# onekeyboard_2.net
KiCad netlist of a schematic drawn in EAGLE
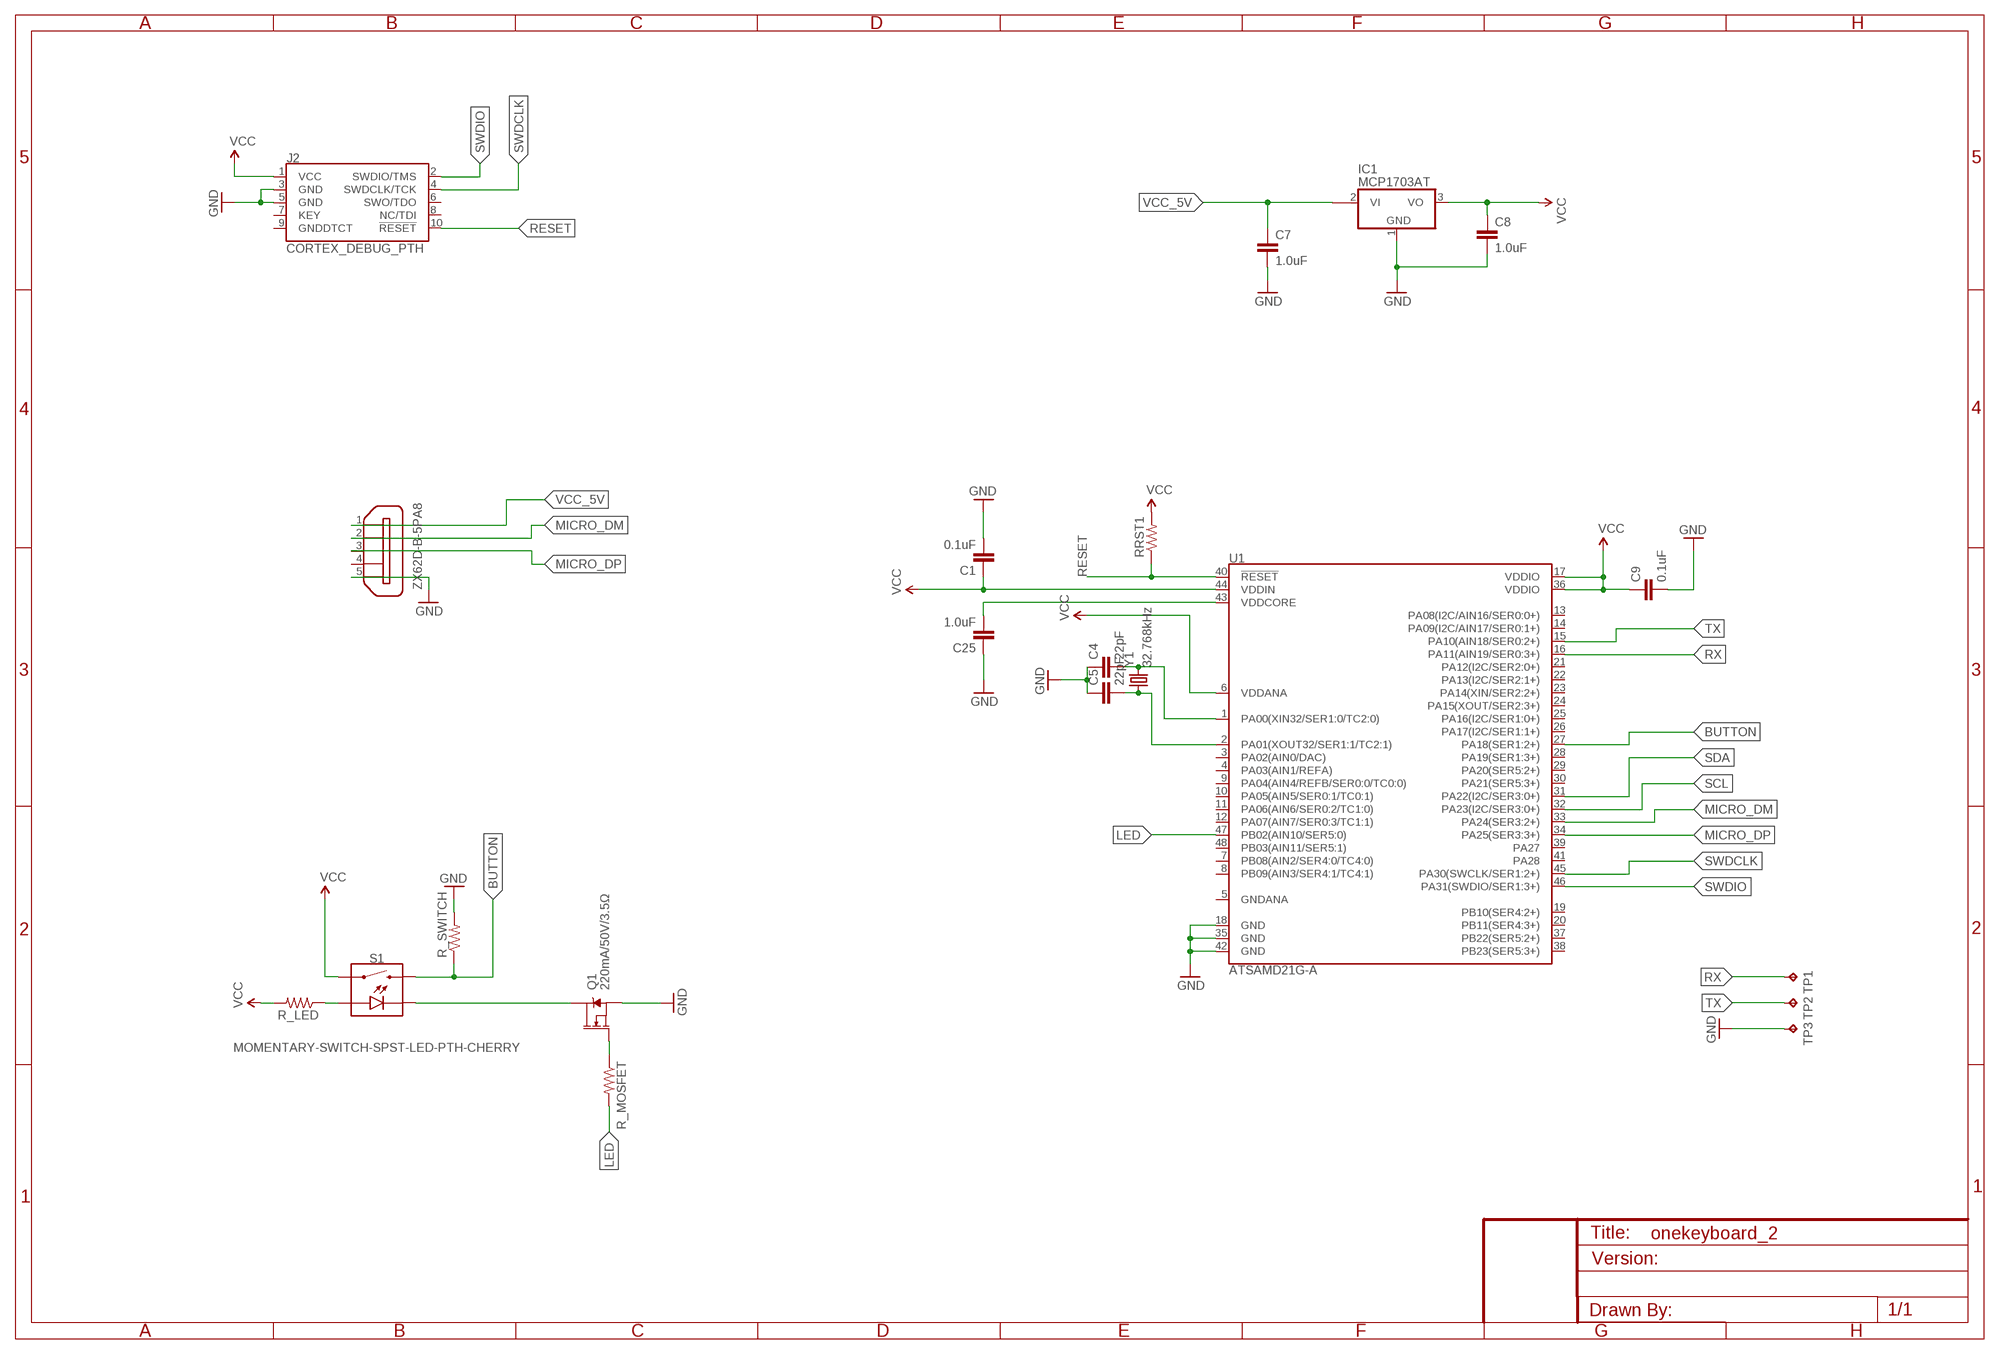
[diagram p0: schematic, sheet 1]

(export (version "E")
  (design (tool "Eeschema 10.0.6"))
  (components
    (comp (ref "C1")
      (value "0.1uF")
      (footprint "eagle-import:0805")
      (libsource (lib "eagle-import") (part "1.0UF-0805-25V-10%"))
    )
    (comp (ref "C4")
      (value "22pF")
      (footprint "eagle-import:0805")
      (libsource (lib "eagle-import") (part "CAP0805"))
    )
    (comp (ref "C5")
      (value "22pF")
      (footprint "eagle-import:0805")
      (libsource (lib "eagle-import") (part "CAP0805"))
    )
    (comp (ref "C7")
      (value "1.0uF")
      (footprint "eagle-import:1206")
      (libsource (lib "eagle-import") (part "1.0UF-1206-50V-10%"))
    )
    (comp (ref "C8")
      (value "1.0uF")
      (footprint "eagle-import:1206")
      (libsource (lib "eagle-import") (part "1.0UF-1206-50V-10%"))
    )
    (comp (ref "C9")
      (value "0.1uF")
      (footprint "eagle-import:0805")
      (libsource (lib "eagle-import") (part "1.0UF-0805-25V-10%"))
    )
    (comp (ref "C25")
      (value "1.0uF")
      (footprint "eagle-import:0805")
      (libsource (lib "eagle-import") (part "1.0UF-0805-25V-10%"))
    )
    (comp (ref "IC1")
      (value "MCP1703AT")
      (footprint "eagle-import:SOT89")
      (libsource (lib "eagle-import") (part "MCP1703MB12"))
    )
    (comp (ref "J2")
      (value "CORTEX_DEBUG_PTH")
      (footprint "eagle-import:2X5-PTH-1.27MM")
      (libsource (lib "eagle-import") (part "CORTEX_DEBUG_PTH"))
    )
    (comp (ref "Q1")
      (value "220mA/50V/3.5Ω")
      (footprint "eagle-import:SOT23-3")
      (libsource (lib "eagle-import") (part "MOSFET-NCH-BSS138"))
    )
    (comp (ref "RRST1")
      (value "RESISTOR0805-RES")
      (footprint "eagle-import:0805")
      (libsource (lib "eagle-import") (part "RESISTOR0805-RES"))
    )
    (comp (ref "R_LED")
      (value "RESISTOR0805-RES")
      (footprint "eagle-import:0805")
      (libsource (lib "eagle-import") (part "RESISTOR0805-RES"))
    )
    (comp (ref "R_MOSFET")
      (value "RESISTOR0805-RES")
      (footprint "eagle-import:0805")
      (libsource (lib "eagle-import") (part "RESISTOR0805-RES"))
    )
    (comp (ref "R_SWITCH")
      (value "RESISTOR0805-RES")
      (footprint "eagle-import:0805")
      (libsource (lib "eagle-import") (part "RESISTOR0805-RES"))
    )
    (comp (ref "S1")
      (value "MOMENTARY-SWITCH-SPST-LED-PTH-CHERRY")
      (footprint "eagle-import:CHERRY-MX-LED")
      (libsource (lib "eagle-import") (part "MOMENTARY-SWITCH-SPST-LED-PTH-CHERRY"))
    )
    (comp (ref "TP1")
      (value "TPB2,54")
      (footprint "eagle-import:B2,54")
      (libsource (lib "eagle-import") (part "TPB2,54"))
    )
    (comp (ref "TP2")
      (value "TPB2,54")
      (footprint "eagle-import:B2,54")
      (libsource (lib "eagle-import") (part "TPB2,54"))
    )
    (comp (ref "TP3")
      (value "TPB2,54")
      (footprint "eagle-import:B2,54")
      (libsource (lib "eagle-import") (part "TPB2,54"))
    )
    (comp (ref "U1")
      (value "ATSAMD21G-A")
      (footprint "eagle-import:TQFP-48")
      (libsource (lib "eagle-import") (part "ATSAMD21G-A"))
    )
    (comp (ref "X2")
      (value "ZX62D-B-5PA8")
      (footprint "eagle-import:ZX62D-B-5PA8")
      (fields (field (name "MF") "Hirose"))
      (libsource (lib "eagle-import") (part "ZX62D-B-5PA8"))
    )
    (comp (ref "Y1")
      (value "32.768kHz")
      (footprint "eagle-import:CRYSTAL-SMD-3.2X1.5MM")
      (libsource (lib "eagle-import") (part "CRYSTAL3.2X1.5MM"))
    )
  )
  (nets
    (net (code "1") (name "BUTTON") (class "Default")
      (node (ref "R_SWITCH") (pin "1") (pinfunction "1_1") (pintype "passive"))
      (node (ref "S1") (pin "S2") (pinfunction "2_S2") (pintype "passive"))
      (node (ref "U1") (pin "27") (pinfunction "PA18(SER1:2+)_27") (pintype "bidirectional"))
    )
    (net (code "2") (name "GND") (class "Default")
      (node (ref "C1") (pin "2") (pinfunction "2_2") (pintype "passive"))
      (node (ref "C25") (pin "1") (pinfunction "1_1") (pintype "passive"))
      (node (ref "C4") (pin "1") (pinfunction "1_1") (pintype "passive"))
      (node (ref "C5") (pin "1") (pinfunction "1_1") (pintype "passive"))
      (node (ref "C7") (pin "2") (pinfunction "2_2") (pintype "passive"))
      (node (ref "C8") (pin "2") (pinfunction "2_2") (pintype "passive"))
      (node (ref "C9") (pin "2") (pinfunction "2_2") (pintype "passive"))
      (node (ref "IC1") (pin "1") (pinfunction "GND_1") (pintype "passive"))
      (node (ref "J2") (pin "3") (pinfunction "GND_3") (pintype "bidirectional"))
      (node (ref "J2") (pin "5") (pinfunction "GND_5") (pintype "bidirectional"))
      (node (ref "Q1") (pin "2") (pinfunction "S_2") (pintype "bidirectional"))
      (node (ref "R_SWITCH") (pin "2") (pinfunction "2_2") (pintype "passive"))
      (node (ref "TP3") (pin "TP") (pinfunction "TP_TP") (pintype "input"))
      (node (ref "U1") (pin "18") (pinfunction "GND_18") (pintype "bidirectional"))
      (node (ref "U1") (pin "35") (pinfunction "GND_35") (pintype "bidirectional"))
      (node (ref "U1") (pin "42") (pinfunction "GND_42") (pintype "bidirectional"))
      (node (ref "X2") (pin "5") (pinfunction "5_5") (pintype "passive"))
    )
    (net (code "3") (name "LED") (class "Default")
      (node (ref "R_MOSFET") (pin "2") (pinfunction "2_2") (pintype "passive"))
      (node (ref "U1") (pin "47") (pinfunction "PB02(AIN10/SER5:0)_47") (pintype "bidirectional"))
    )
    (net (code "4") (name "MICRO_DM") (class "Default")
      (node (ref "U1") (pin "33") (pinfunction "PA24(SER3:2+)_33") (pintype "bidirectional"))
      (node (ref "X2") (pin "2") (pinfunction "2_2") (pintype "passive"))
    )
    (net (code "5") (name "MICRO_DP") (class "Default")
      (node (ref "U1") (pin "34") (pinfunction "PA25(SER3:3+)_34") (pintype "bidirectional"))
      (node (ref "X2") (pin "3") (pinfunction "3_3") (pintype "passive"))
    )
    (net (code "6") (name "Net-(Q1-D)") (class "Default")
      (node (ref "Q1") (pin "3") (pinfunction "D_3") (pintype "bidirectional"))
      (node (ref "S1") (pin "K") (pinfunction "C_K") (pintype "passive"))
    )
    (net (code "7") (name "Net-(Q1-G)") (class "Default")
      (node (ref "Q1") (pin "1") (pinfunction "G_1") (pintype "bidirectional"))
      (node (ref "R_MOSFET") (pin "1") (pinfunction "1_1") (pintype "passive"))
    )
    (net (code "8") (name "Net-(R_LED-Pad1)") (class "Default")
      (node (ref "R_LED") (pin "1") (pinfunction "1_1") (pintype "passive"))
      (node (ref "S1") (pin "A") (pinfunction "A_A") (pintype "passive"))
    )
    (net (code "9") (name "Net-(U1-PA00(XIN32{slash}SER1:0{slash}TC2:0))") (class "Default")
      (node (ref "C4") (pin "2") (pinfunction "2_2") (pintype "passive"))
      (node (ref "U1") (pin "1") (pinfunction "PA00(XIN32/SER1:0/TC2:0)_1") (pintype "bidirectional"))
      (node (ref "Y1") (pin "P$2") (pinfunction "2_P$2") (pintype "passive"))
    )
    (net (code "10") (name "Net-(U1-PA01(XOUT32{slash}SER1:1{slash}TC2:1))") (class "Default")
      (node (ref "C5") (pin "2") (pinfunction "2_2") (pintype "passive"))
      (node (ref "U1") (pin "2") (pinfunction "PA01(XOUT32/SER1:1/TC2:1)_2") (pintype "bidirectional"))
      (node (ref "Y1") (pin "P$1") (pinfunction "1_P$1") (pintype "passive"))
    )
    (net (code "11") (name "Net-(U1-VDDCORE)") (class "Default")
      (node (ref "C25") (pin "2") (pinfunction "2_2") (pintype "passive"))
      (node (ref "U1") (pin "43") (pinfunction "VDDCORE_43") (pintype "bidirectional"))
    )
    (net (code "12") (name "RESET") (class "Default")
      (node (ref "J2") (pin "10") (pinfunction "~{RESET}_10") (pintype "bidirectional"))
      (node (ref "RRST1") (pin "1") (pinfunction "1_1") (pintype "passive"))
      (node (ref "U1") (pin "40") (pinfunction "~{RESET}_40") (pintype "bidirectional"))
    )
    (net (code "13") (name "RX") (class "Default")
      (node (ref "TP1") (pin "TP") (pinfunction "TP_TP") (pintype "input"))
      (node (ref "U1") (pin "16") (pinfunction "PA11(AIN19/SER0:3+)_16") (pintype "bidirectional"))
    )
    (net (code "14") (name "SCL") (class "Default")
      (node (ref "U1") (pin "32") (pinfunction "PA23(I2C/SER3:0+)_32") (pintype "bidirectional"))
    )
    (net (code "15") (name "SDA") (class "Default")
      (node (ref "U1") (pin "31") (pinfunction "PA22(I2C/SER3:0+)_31") (pintype "bidirectional"))
    )
    (net (code "16") (name "SWDCLK") (class "Default")
      (node (ref "J2") (pin "4") (pinfunction "SWDCLK/TCK_4") (pintype "bidirectional"))
      (node (ref "U1") (pin "45") (pinfunction "PA30(SWCLK/SER1:2+)_45") (pintype "bidirectional"))
    )
    (net (code "17") (name "SWDIO") (class "Default")
      (node (ref "J2") (pin "2") (pinfunction "SWDIO/TMS_2") (pintype "bidirectional"))
      (node (ref "U1") (pin "46") (pinfunction "PA31(SWDIO/SER1:3+)_46") (pintype "bidirectional"))
    )
    (net (code "18") (name "TX") (class "Default")
      (node (ref "TP2") (pin "TP") (pinfunction "TP_TP") (pintype "input"))
      (node (ref "U1") (pin "15") (pinfunction "PA10(AIN18/SER0:2+)_15") (pintype "bidirectional"))
    )
    (net (code "19") (name "VCC") (class "Default")
      (node (ref "C1") (pin "1") (pinfunction "1_1") (pintype "passive"))
      (node (ref "C8") (pin "1") (pinfunction "1_1") (pintype "passive"))
      (node (ref "C9") (pin "1") (pinfunction "1_1") (pintype "passive"))
      (node (ref "IC1") (pin "3") (pinfunction "VO_3") (pintype "passive"))
      (node (ref "J2") (pin "1") (pinfunction "VCC_1") (pintype "bidirectional"))
      (node (ref "RRST1") (pin "2") (pinfunction "2_2") (pintype "passive"))
      (node (ref "R_LED") (pin "2") (pinfunction "2_2") (pintype "passive"))
      (node (ref "S1") (pin "S1") (pinfunction "1_S1") (pintype "passive"))
      (node (ref "U1") (pin "17") (pinfunction "VDDIO_17") (pintype "bidirectional"))
      (node (ref "U1") (pin "36") (pinfunction "VDDIO_36") (pintype "bidirectional"))
      (node (ref "U1") (pin "44") (pinfunction "VDDIN_44") (pintype "bidirectional"))
      (node (ref "U1") (pin "6") (pinfunction "VDDANA_6") (pintype "bidirectional"))
    )
    (net (code "20") (name "VCC_5V") (class "Default")
      (node (ref "C7") (pin "1") (pinfunction "1_1") (pintype "passive"))
      (node (ref "IC1") (pin "2@1") (pinfunction "VI1_2@1") (pintype "input"))
      (node (ref "X2") (pin "1") (pinfunction "1_1") (pintype "passive"))
    )
    (net (code "21") (name "unconnected-(IC1-VI-Pad2)") (class "Default")
      (node (ref "IC1") (pin "2") (pinfunction "VI_2") (pintype "input"))
    )
    (net (code "22") (name "unconnected-(J2-GNDDTCT-Pad9)") (class "Default")
      (node (ref "J2") (pin "9") (pinfunction "GNDDTCT_9") (pintype "bidirectional"))
    )
    (net (code "23") (name "unconnected-(J2-KEY-Pad7)") (class "Default")
      (node (ref "J2") (pin "7") (pinfunction "KEY_7") (pintype "bidirectional"))
    )
    (net (code "24") (name "unconnected-(J2-NC{slash}TDI-Pad8)") (class "Default")
      (node (ref "J2") (pin "8") (pinfunction "NC/TDI_8") (pintype "bidirectional"))
    )
    (net (code "25") (name "unconnected-(J2-SWO{slash}TDO-Pad6)") (class "Default")
      (node (ref "J2") (pin "6") (pinfunction "SWO/TDO_6") (pintype "bidirectional"))
    )
    (net (code "26") (name "unconnected-(U1-GNDANA-Pad5)") (class "Default")
      (node (ref "U1") (pin "5") (pinfunction "GNDANA_5") (pintype "bidirectional"))
    )
    (net (code "27") (name "unconnected-(U1-PA02(AIN0{slash}DAC)-Pad3)") (class "Default")
      (node (ref "U1") (pin "3") (pinfunction "PA02(AIN0/DAC)_3") (pintype "bidirectional"))
    )
    (net (code "28") (name "unconnected-(U1-PA03(AIN1{slash}REFA)-Pad4)") (class "Default")
      (node (ref "U1") (pin "4") (pinfunction "PA03(AIN1/REFA)_4") (pintype "bidirectional"))
    )
    (net (code "29") (name "unconnected-(U1-PA04(AIN4{slash}REFB{slash}SER0:0{slash}TC0:0)-Pad9)") (class "Default")
      (node (ref "U1") (pin "9") (pinfunction "PA04(AIN4/REFB/SER0:0/TC0:0)_9") (pintype "bidirectional"))
    )
    (net (code "30") (name "unconnected-(U1-PA05(AIN5{slash}SER0:1{slash}TC0:1)-Pad10)") (class "Default")
      (node (ref "U1") (pin "10") (pinfunction "PA05(AIN5/SER0:1/TC0:1)_10") (pintype "bidirectional"))
    )
    (net (code "31") (name "unconnected-(U1-PA06(AIN6{slash}SER0:2{slash}TC1:0)-Pad11)") (class "Default")
      (node (ref "U1") (pin "11") (pinfunction "PA06(AIN6/SER0:2/TC1:0)_11") (pintype "bidirectional"))
    )
    (net (code "32") (name "unconnected-(U1-PA07(AIN7{slash}SER0:3{slash}TC1:1)-Pad12)") (class "Default")
      (node (ref "U1") (pin "12") (pinfunction "PA07(AIN7/SER0:3/TC1:1)_12") (pintype "bidirectional"))
    )
    (net (code "33") (name "unconnected-(U1-PA08(I2C{slash}AIN16{slash}SER0:0+)-Pad13)") (class "Default")
      (node (ref "U1") (pin "13") (pinfunction "PA08(I2C/AIN16/SER0:0+)_13") (pintype "bidirectional"))
    )
    (net (code "34") (name "unconnected-(U1-PA09(I2C{slash}AIN17{slash}SER0:1+)-Pad14)") (class "Default")
      (node (ref "U1") (pin "14") (pinfunction "PA09(I2C/AIN17/SER0:1+)_14") (pintype "bidirectional"))
    )
    (net (code "35") (name "unconnected-(U1-PA12(I2C{slash}SER2:0+)-Pad21)") (class "Default")
      (node (ref "U1") (pin "21") (pinfunction "PA12(I2C/SER2:0+)_21") (pintype "bidirectional"))
    )
    (net (code "36") (name "unconnected-(U1-PA13(I2C{slash}SER2:1+)-Pad22)") (class "Default")
      (node (ref "U1") (pin "22") (pinfunction "PA13(I2C/SER2:1+)_22") (pintype "bidirectional"))
    )
    (net (code "37") (name "unconnected-(U1-PA14(XIN{slash}SER2:2+)-Pad23)") (class "Default")
      (node (ref "U1") (pin "23") (pinfunction "PA14(XIN/SER2:2+)_23") (pintype "bidirectional"))
    )
    (net (code "38") (name "unconnected-(U1-PA15(XOUT{slash}SER2:3+)-Pad24)") (class "Default")
      (node (ref "U1") (pin "24") (pinfunction "PA15(XOUT/SER2:3+)_24") (pintype "bidirectional"))
    )
    (net (code "39") (name "unconnected-(U1-PA16(I2C{slash}SER1:0+)-Pad25)") (class "Default")
      (node (ref "U1") (pin "25") (pinfunction "PA16(I2C/SER1:0+)_25") (pintype "bidirectional"))
    )
    (net (code "40") (name "unconnected-(U1-PA17(I2C{slash}SER1:1+)-Pad26)") (class "Default")
      (node (ref "U1") (pin "26") (pinfunction "PA17(I2C/SER1:1+)_26") (pintype "bidirectional"))
    )
    (net (code "41") (name "unconnected-(U1-PA19(SER1:3+)-Pad28)") (class "Default")
      (node (ref "U1") (pin "28") (pinfunction "PA19(SER1:3+)_28") (pintype "bidirectional"))
    )
    (net (code "42") (name "unconnected-(U1-PA20(SER5:2+)-Pad29)") (class "Default")
      (node (ref "U1") (pin "29") (pinfunction "PA20(SER5:2+)_29") (pintype "bidirectional"))
    )
    (net (code "43") (name "unconnected-(U1-PA21(SER5:3+)-Pad30)") (class "Default")
      (node (ref "U1") (pin "30") (pinfunction "PA21(SER5:3+)_30") (pintype "bidirectional"))
    )
    (net (code "44") (name "unconnected-(U1-PA27-Pad39)") (class "Default")
      (node (ref "U1") (pin "39") (pinfunction "PA27_39") (pintype "bidirectional"))
    )
    (net (code "45") (name "unconnected-(U1-PA28-Pad41)") (class "Default")
      (node (ref "U1") (pin "41") (pinfunction "PA28_41") (pintype "bidirectional"))
    )
    (net (code "46") (name "unconnected-(U1-PB03(AIN11{slash}SER5:1)-Pad48)") (class "Default")
      (node (ref "U1") (pin "48") (pinfunction "PB03(AIN11/SER5:1)_48") (pintype "bidirectional"))
    )
    (net (code "47") (name "unconnected-(U1-PB08(AIN2{slash}SER4:0{slash}TC4:0)-Pad7)") (class "Default")
      (node (ref "U1") (pin "7") (pinfunction "PB08(AIN2/SER4:0/TC4:0)_7") (pintype "bidirectional"))
    )
    (net (code "48") (name "unconnected-(U1-PB09(AIN3{slash}SER4:1{slash}TC4:1)-Pad8)") (class "Default")
      (node (ref "U1") (pin "8") (pinfunction "PB09(AIN3/SER4:1/TC4:1)_8") (pintype "bidirectional"))
    )
    (net (code "49") (name "unconnected-(U1-PB10(SER4:2+)-Pad19)") (class "Default")
      (node (ref "U1") (pin "19") (pinfunction "PB10(SER4:2+)_19") (pintype "bidirectional"))
    )
    (net (code "50") (name "unconnected-(U1-PB11(SER4:3+)-Pad20)") (class "Default")
      (node (ref "U1") (pin "20") (pinfunction "PB11(SER4:3+)_20") (pintype "bidirectional"))
    )
    (net (code "51") (name "unconnected-(U1-PB22(SER5:2+)-Pad37)") (class "Default")
      (node (ref "U1") (pin "37") (pinfunction "PB22(SER5:2+)_37") (pintype "bidirectional"))
    )
    (net (code "52") (name "unconnected-(U1-PB23(SER5:3+)-Pad38)") (class "Default")
      (node (ref "U1") (pin "38") (pinfunction "PB23(SER5:3+)_38") (pintype "bidirectional"))
    )
    (net (code "53") (name "unconnected-(X2-Pad4)") (class "Default")
      (node (ref "X2") (pin "4") (pinfunction "4_4") (pintype "passive"))
    )
  )
)
